# RXV2.net
KiCad netlist of a schematic drawn in EAGLE
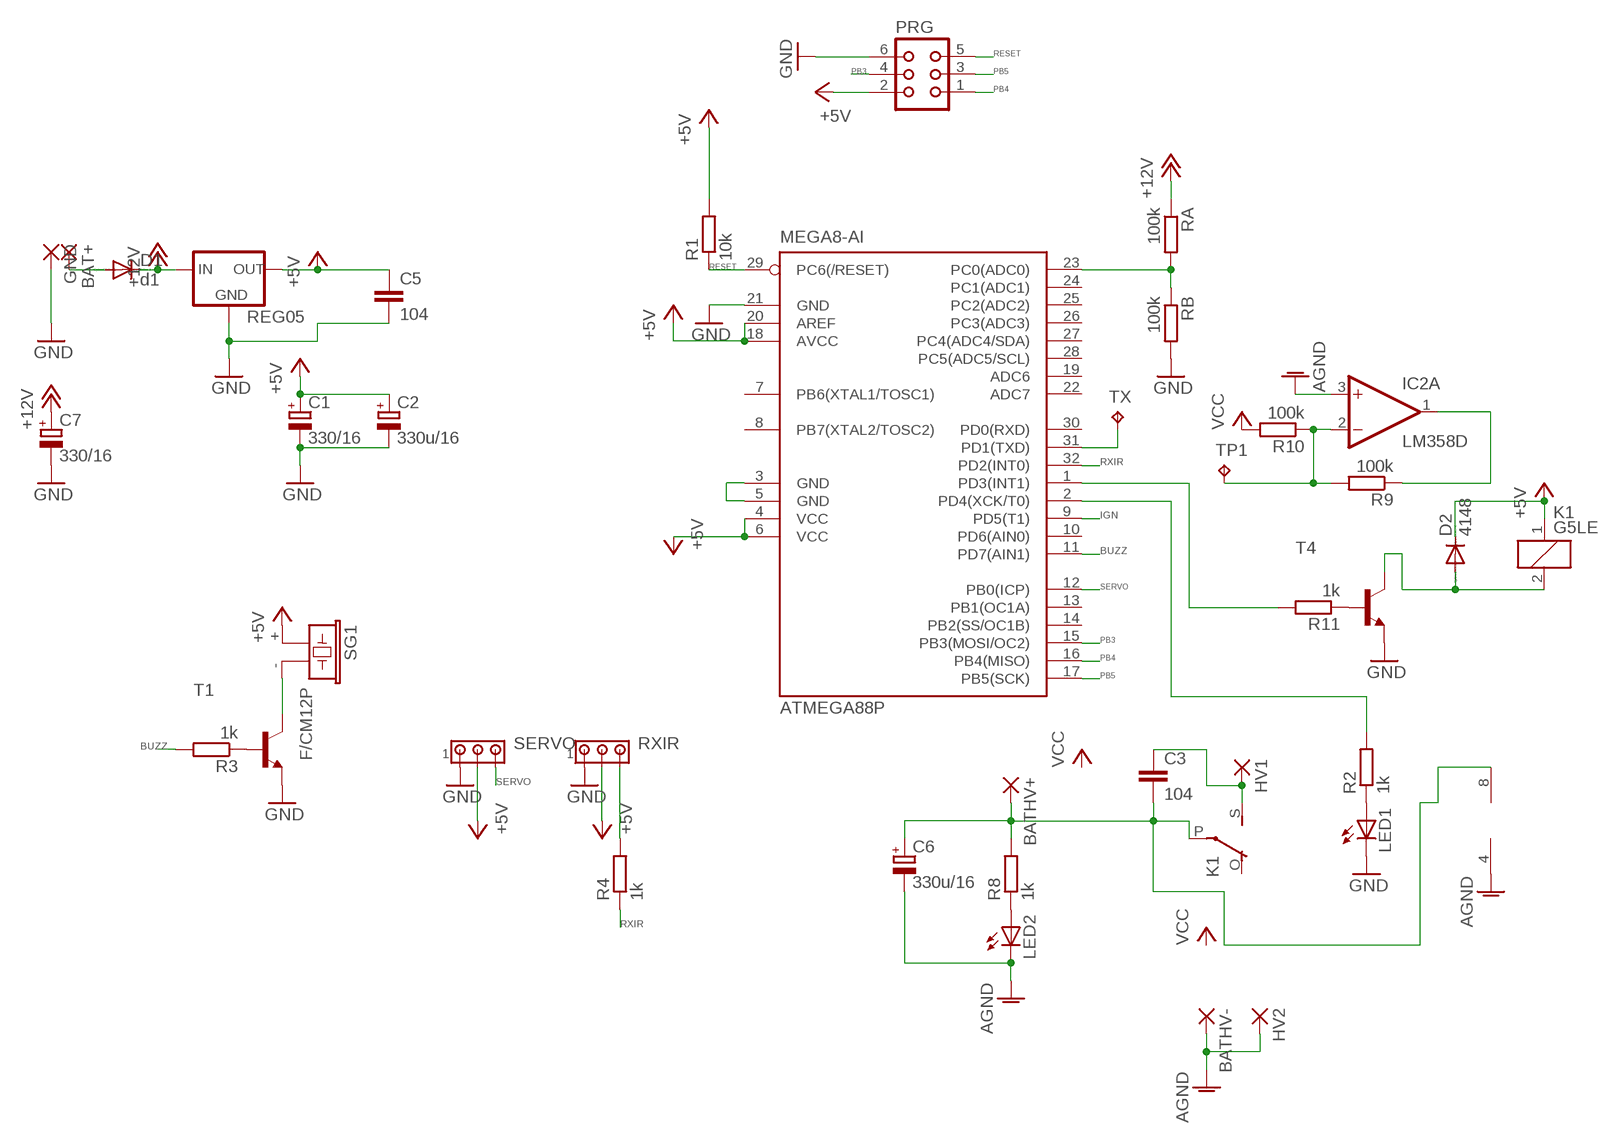
[diagram p0: schematic, sheet 1]

(export (version "E")
  (design (tool "Eeschema 10.0.6"))
  (components
    (comp (ref "ATMEGA88P")
      (value "MEGA8-AI")
      (footprint "eagle-import:TQFP32-08")
      (fields (field (name "MPN") "ATMEGA8-16AU"))
      (libsource (lib "eagle-import") (part "MEGA8-AI"))
    )
    (comp (ref "BAT+")
      (value "SMD5")
      (footprint "eagle-import:SMD2,54-5,08")
      (libsource (lib "eagle-import") (part "SMD5"))
    )
    (comp (ref "BATHV+")
      (value "SMD5")
      (footprint "eagle-import:SMD2,54-5,08")
      (libsource (lib "eagle-import") (part "SMD5"))
    )
    (comp (ref "BATHV-")
      (value "SMD5")
      (footprint "eagle-import:SMD2,54-5,08")
      (libsource (lib "eagle-import") (part "SMD5"))
    )
    (comp (ref "C1")
      (value "330/16")
      (footprint "eagle-import:E2,5-7")
      (libsource (lib "eagle-import") (part "CPOL-EUE2.5-7"))
    )
    (comp (ref "C2")
      (value "330u/16")
      (footprint "eagle-import:E2,5-6")
      (libsource (lib "eagle-import") (part "CPOL-EUE2.5-6"))
    )
    (comp (ref "C3")
      (value "104")
      (footprint "eagle-import:C0805")
      (libsource (lib "eagle-import") (part "C-EUC0805"))
    )
    (comp (ref "C5")
      (value "104")
      (footprint "eagle-import:C2.5-2")
      (libsource (lib "eagle-import") (part "C2.5/2"))
    )
    (comp (ref "C6")
      (value "330u/16")
      (footprint "eagle-import:E2,5-6")
      (libsource (lib "eagle-import") (part "CPOL-EUE2.5-6"))
    )
    (comp (ref "C7")
      (value "330/16")
      (footprint "eagle-import:E2,5-7")
      (libsource (lib "eagle-import") (part "CPOL-EUE2.5-7"))
    )
    (comp (ref "D1")
      (value "d1")
      (footprint "eagle-import:SOD-123_MINI-SMA")
      (libsource (lib "eagle-import") (part "CGRM400-G7"))
    )
    (comp (ref "D2")
      (value "4148")
      (footprint "eagle-import:DO35-7")
      (libsource (lib "eagle-import") (part "1N4148DO35-7"))
    )
    (comp (ref "GND")
      (value "SMD5")
      (footprint "eagle-import:SMD2,54-5,08")
      (libsource (lib "eagle-import") (part "SMD5"))
    )
    (comp (ref "HV1")
      (value "SMD5")
      (footprint "eagle-import:SMD2,54-5,08")
      (libsource (lib "eagle-import") (part "SMD5"))
    )
    (comp (ref "HV2")
      (value "SMD5")
      (footprint "eagle-import:SMD2,54-5,08")
      (libsource (lib "eagle-import") (part "SMD5"))
    )
    (comp (ref "IC2")
      (value "LM358D")
      (footprint "eagle-import:SO08")
      (libsource (lib "eagle-import") (part "LM358D"))
    )
    (comp (ref "K1")
      (value "G5LE")
      (footprint "eagle-import:G5LE")
      (libsource (lib "eagle-import") (part "G5LE"))
    )
    (comp (ref "LED1")
      (value "LEDCHIPLED_0805")
      (footprint "eagle-import:CHIPLED_0805")
      (libsource (lib "eagle-import") (part "LEDCHIPLED_0805"))
    )
    (comp (ref "LED2")
      (value "LEDCHIPLED_0805")
      (footprint "eagle-import:CHIPLED_0805")
      (libsource (lib "eagle-import") (part "LEDCHIPLED_0805"))
    )
    (comp (ref "PRG")
      (value "CON06")
      (footprint "eagle-import:CON06")
      (libsource (lib "eagle-import") (part "CON06"))
    )
    (comp (ref "R1")
      (value "10k")
      (footprint "eagle-import:M1206")
      (libsource (lib "eagle-import") (part "R-EU_M1206"))
    )
    (comp (ref "R2")
      (value "1k")
      (footprint "eagle-import:M1206")
      (libsource (lib "eagle-import") (part "R-EU_M1206"))
    )
    (comp (ref "R3")
      (value "1k")
      (footprint "eagle-import:M1206")
      (libsource (lib "eagle-import") (part "R-EU_M1206"))
    )
    (comp (ref "R4")
      (value "1k")
      (footprint "eagle-import:M1206")
      (libsource (lib "eagle-import") (part "R-EU_M1206"))
    )
    (comp (ref "R8")
      (value "1k")
      (footprint "eagle-import:M1206")
      (libsource (lib "eagle-import") (part "R-EU_M1206"))
    )
    (comp (ref "R9")
      (value "100k")
      (footprint "eagle-import:M1206")
      (libsource (lib "eagle-import") (part "R-EU_M1206"))
    )
    (comp (ref "R10")
      (value "100k")
      (footprint "eagle-import:M1206")
      (libsource (lib "eagle-import") (part "R-EU_M1206"))
    )
    (comp (ref "R11")
      (value "1k")
      (footprint "eagle-import:M1206")
      (libsource (lib "eagle-import") (part "R-EU_M1206"))
    )
    (comp (ref "RA")
      (value "100k")
      (footprint "eagle-import:M1206")
      (libsource (lib "eagle-import") (part "R-EU_M1206"))
    )
    (comp (ref "RB")
      (value "100k")
      (footprint "eagle-import:M1206")
      (libsource (lib "eagle-import") (part "R-EU_M1206"))
    )
    (comp (ref "REG05")
      (value "78XXS")
      (footprint "eagle-import:78XXS")
      (libsource (lib "eagle-import") (part "78XXS"))
    )
    (comp (ref "RXIR")
      (value "MTA03-100")
      (footprint "eagle-import:10X03MTA")
      (libsource (lib "eagle-import") (part "MTA03-100"))
    )
    (comp (ref "SERVO")
      (value "MTA03-100")
      (footprint "eagle-import:10X03MTA")
      (libsource (lib "eagle-import") (part "MTA03-100"))
    )
    (comp (ref "SG1")
      (value "F/CM12P")
      (footprint "eagle-import:F_CM12P")
      (libsource (lib "eagle-import") (part "F/CM12P"))
    )
    (comp (ref "T1")
      (value "MMBT2222ALT1-NPN-SOT23-BEC")
      (footprint "eagle-import:SOT23-BEC")
      (libsource (lib "eagle-import") (part "-NPN-SOT23-BECMMBT2222ALT1"))
    )
    (comp (ref "T4")
      (value "MMBT2222ALT1-NPN-SOT23-BEC")
      (footprint "eagle-import:SOT23-BEC")
      (libsource (lib "eagle-import") (part "-NPN-SOT23-BECMMBT2222ALT1"))
    )
    (comp (ref "TP1")
      (value "TPTP19R")
      (footprint "eagle-import:TP19R")
      (libsource (lib "eagle-import") (part "TPTP19R"))
    )
    (comp (ref "TX")
      (value "TPTP19R")
      (footprint "eagle-import:TP19R")
      (libsource (lib "eagle-import") (part "TPTP19R"))
    )
  )
  (nets
    (net (code "1") (name "+5V") (class "Default")
      (node (ref "ATMEGA88P") (pin "18") (pinfunction "AVCC_18") (pintype "power_in"))
      (node (ref "ATMEGA88P") (pin "20") (pinfunction "AREF_20") (pintype "passive"))
      (node (ref "ATMEGA88P") (pin "4") (pinfunction "VCC_4") (pintype "power_in"))
      (node (ref "ATMEGA88P") (pin "6") (pinfunction "VCC_6") (pintype "power_in"))
      (node (ref "C1") (pin "+") (pinfunction "+_+") (pintype "passive"))
      (node (ref "C2") (pin "+") (pinfunction "+_+") (pintype "passive"))
      (node (ref "C5") (pin "1") (pinfunction "1_1") (pintype "passive"))
      (node (ref "D2") (pin "C") (pinfunction "C_C") (pintype "passive"))
      (node (ref "K1") (pin "1") (pinfunction "1_1") (pintype "passive"))
      (node (ref "PRG") (pin "2") (pinfunction "2_2") (pintype "passive"))
      (node (ref "R1") (pin "2") (pinfunction "2_2") (pintype "passive"))
      (node (ref "REG05") (pin "OUT") (pinfunction "OUT_OUT") (pintype "passive"))
      (node (ref "RXIR") (pin "2") (pinfunction "2_2") (pintype "passive"))
      (node (ref "SERVO") (pin "2") (pinfunction "2_2") (pintype "passive"))
      (node (ref "SG1") (pin "+") (pinfunction "1_+") (pintype "passive"))
    )
    (net (code "2") (name "+12V") (class "Default")
      (node (ref "C7") (pin "+") (pinfunction "+_+") (pintype "passive"))
      (node (ref "D1") (pin "C") (pinfunction "C_C") (pintype "passive"))
      (node (ref "RA") (pin "1") (pinfunction "1_1") (pintype "passive"))
      (node (ref "REG05") (pin "IN") (pinfunction "IN_IN") (pintype "input"))
    )
    (net (code "3") (name "/BUZZ") (class "Default")
      (node (ref "ATMEGA88P") (pin "11") (pinfunction "PD7(AIN1)_11") (pintype "bidirectional"))
      (node (ref "R3") (pin "2") (pinfunction "2_2") (pintype "passive"))
    )
    (net (code "4") (name "/IGN") (class "Default")
      (node (ref "ATMEGA88P") (pin "9") (pinfunction "PD5(T1)_9") (pintype "bidirectional"))
    )
    (net (code "5") (name "/PB3") (class "Default")
      (node (ref "ATMEGA88P") (pin "15") (pinfunction "PB3(MOSI/OC2)_15") (pintype "bidirectional"))
      (node (ref "PRG") (pin "4") (pinfunction "4_4") (pintype "passive"))
    )
    (net (code "6") (name "/PB4") (class "Default")
      (node (ref "ATMEGA88P") (pin "16") (pinfunction "PB4(MISO)_16") (pintype "bidirectional"))
      (node (ref "PRG") (pin "1") (pinfunction "1_1") (pintype "passive"))
    )
    (net (code "7") (name "/PB5") (class "Default")
      (node (ref "ATMEGA88P") (pin "17") (pinfunction "PB5(SCK)_17") (pintype "bidirectional"))
      (node (ref "PRG") (pin "3") (pinfunction "3_3") (pintype "passive"))
    )
    (net (code "8") (name "/RESET") (class "Default")
      (node (ref "ATMEGA88P") (pin "29") (pinfunction "PC6(/RESET)_29") (pintype "bidirectional"))
      (node (ref "PRG") (pin "5") (pinfunction "5_5") (pintype "passive"))
      (node (ref "R1") (pin "1") (pinfunction "1_1") (pintype "passive"))
    )
    (net (code "9") (name "/RXIR") (class "Default")
      (node (ref "ATMEGA88P") (pin "32") (pinfunction "PD2(INT0)_32") (pintype "bidirectional"))
      (node (ref "R4") (pin "1") (pinfunction "1_1") (pintype "passive"))
    )
    (net (code "10") (name "/SERVO") (class "Default")
      (node (ref "ATMEGA88P") (pin "12") (pinfunction "PB0(ICP)_12") (pintype "bidirectional"))
      (node (ref "SERVO") (pin "3") (pinfunction "3_3") (pintype "passive"))
    )
    (net (code "11") (name "AGND") (class "Default")
      (node (ref "BATHV-") (pin "1") (pinfunction "P_1") (pintype "passive"))
      (node (ref "C6") (pin "-") (pinfunction "-_-") (pintype "passive"))
      (node (ref "HV2") (pin "1") (pinfunction "P_1") (pintype "passive"))
      (node (ref "IC2") (pin "3") (pinfunction "+IN_3") (pintype "input"))
      (node (ref "IC2") (pin "4") (pinfunction "V-_4") (pintype "power_in"))
      (node (ref "LED2") (pin "C") (pinfunction "C_C") (pintype "passive"))
    )
    (net (code "12") (name "GND") (class "Default")
      (node (ref "ATMEGA88P") (pin "21") (pinfunction "GND_21") (pintype "power_in"))
      (node (ref "C1") (pin "-") (pinfunction "-_-") (pintype "passive"))
      (node (ref "C2") (pin "-") (pinfunction "-_-") (pintype "passive"))
      (node (ref "C5") (pin "2") (pinfunction "2_2") (pintype "passive"))
      (node (ref "C7") (pin "-") (pinfunction "-_-") (pintype "passive"))
      (node (ref "GND") (pin "1") (pinfunction "P_1") (pintype "passive"))
      (node (ref "LED1") (pin "C") (pinfunction "C_C") (pintype "passive"))
      (node (ref "PRG") (pin "6") (pinfunction "6_6") (pintype "passive"))
      (node (ref "RB") (pin "2") (pinfunction "2_2") (pintype "passive"))
      (node (ref "REG05") (pin "GND") (pinfunction "GND_GND") (pintype "input"))
      (node (ref "RXIR") (pin "1") (pinfunction "1_1") (pintype "passive"))
      (node (ref "SERVO") (pin "1") (pinfunction "1_1") (pintype "passive"))
      (node (ref "T1") (pin "E") (pinfunction "E_E") (pintype "passive"))
      (node (ref "T4") (pin "E") (pinfunction "E_E") (pintype "passive"))
    )
    (net (code "13") (name "Net-(ATMEGA88P-GND-Pad3)") (class "Default")
      (node (ref "ATMEGA88P") (pin "3") (pinfunction "GND_3") (pintype "power_in"))
      (node (ref "ATMEGA88P") (pin "5") (pinfunction "GND_5") (pintype "power_in"))
    )
    (net (code "14") (name "Net-(ATMEGA88P-PC0(ADC0))") (class "Default")
      (node (ref "ATMEGA88P") (pin "23") (pinfunction "PC0(ADC0)_23") (pintype "bidirectional"))
      (node (ref "RA") (pin "2") (pinfunction "2_2") (pintype "passive"))
      (node (ref "RB") (pin "1") (pinfunction "1_1") (pintype "passive"))
    )
    (net (code "15") (name "Net-(ATMEGA88P-PD1(TXD))") (class "Default")
      (node (ref "ATMEGA88P") (pin "31") (pinfunction "PD1(TXD)_31") (pintype "bidirectional"))
      (node (ref "TX") (pin "TP") (pinfunction "TP_TP") (pintype "input"))
    )
    (net (code "16") (name "Net-(ATMEGA88P-PD3(INT1))") (class "Default")
      (node (ref "ATMEGA88P") (pin "1") (pinfunction "PD3(INT1)_1") (pintype "bidirectional"))
      (node (ref "R11") (pin "2") (pinfunction "2_2") (pintype "passive"))
    )
    (net (code "17") (name "Net-(ATMEGA88P-PD4(XCK{slash}T0))") (class "Default")
      (node (ref "ATMEGA88P") (pin "2") (pinfunction "PD4(XCK/T0)_2") (pintype "bidirectional"))
      (node (ref "R2") (pin "2") (pinfunction "2_2") (pintype "passive"))
    )
    (net (code "18") (name "Net-(BAT+-P)") (class "Default")
      (node (ref "BAT+") (pin "1") (pinfunction "P_1") (pintype "passive"))
      (node (ref "D1") (pin "A") (pinfunction "A_A") (pintype "passive"))
    )
    (net (code "19") (name "Net-(BATHV+-P)") (class "Default")
      (node (ref "BATHV+") (pin "1") (pinfunction "P_1") (pintype "passive"))
      (node (ref "C3") (pin "2") (pinfunction "2_2") (pintype "passive"))
      (node (ref "C6") (pin "+") (pinfunction "+_+") (pintype "passive"))
      (node (ref "IC2") (pin "8") (pinfunction "V+_8") (pintype "power_in"))
      (node (ref "K1") (pin "P") (pinfunction "P_P") (pintype "passive"))
      (node (ref "R8") (pin "2") (pinfunction "2_2") (pintype "passive"))
    )
    (net (code "20") (name "Net-(D2-PadA)") (class "Default")
      (node (ref "D2") (pin "A") (pinfunction "A_A") (pintype "passive"))
      (node (ref "K1") (pin "2") (pinfunction "2_2") (pintype "passive"))
      (node (ref "T4") (pin "C") (pinfunction "C_C") (pintype "passive"))
    )
    (net (code "21") (name "Net-(HV1-P)") (class "Default")
      (node (ref "C3") (pin "1") (pinfunction "1_1") (pintype "passive"))
      (node (ref "HV1") (pin "1") (pinfunction "P_1") (pintype "passive"))
      (node (ref "K1") (pin "S") (pinfunction "S_S") (pintype "passive"))
    )
    (net (code "22") (name "Net-(IC2A--IN)") (class "Default")
      (node (ref "IC2") (pin "2") (pinfunction "-IN_2") (pintype "input"))
      (node (ref "R10") (pin "1") (pinfunction "1_1") (pintype "passive"))
      (node (ref "R9") (pin "2") (pinfunction "2_2") (pintype "passive"))
      (node (ref "TP1") (pin "TP") (pinfunction "TP_TP") (pintype "input"))
    )
    (net (code "23") (name "Net-(IC2A-OUT)") (class "Default")
      (node (ref "IC2") (pin "1") (pinfunction "OUT_1") (pintype "output"))
      (node (ref "R9") (pin "1") (pinfunction "1_1") (pintype "passive"))
    )
    (net (code "24") (name "Net-(LED1-PadA)") (class "Default")
      (node (ref "LED1") (pin "A") (pinfunction "A_A") (pintype "passive"))
      (node (ref "R2") (pin "1") (pinfunction "1_1") (pintype "passive"))
    )
    (net (code "25") (name "Net-(LED2-PadA)") (class "Default")
      (node (ref "LED2") (pin "A") (pinfunction "A_A") (pintype "passive"))
      (node (ref "R8") (pin "1") (pinfunction "1_1") (pintype "passive"))
    )
    (net (code "26") (name "Net-(R3-Pad1)") (class "Default")
      (node (ref "R3") (pin "1") (pinfunction "1_1") (pintype "passive"))
      (node (ref "T1") (pin "B") (pinfunction "B_B") (pintype "passive"))
    )
    (net (code "27") (name "Net-(R4-Pad2)") (class "Default")
      (node (ref "R4") (pin "2") (pinfunction "2_2") (pintype "passive"))
      (node (ref "RXIR") (pin "3") (pinfunction "3_3") (pintype "passive"))
    )
    (net (code "28") (name "Net-(R11-Pad1)") (class "Default")
      (node (ref "R11") (pin "1") (pinfunction "1_1") (pintype "passive"))
      (node (ref "T4") (pin "B") (pinfunction "B_B") (pintype "passive"))
    )
    (net (code "29") (name "Net-(SG1-2)") (class "Default")
      (node (ref "SG1") (pin "-") (pinfunction "2_-") (pintype "passive"))
      (node (ref "T1") (pin "C") (pinfunction "C_C") (pintype "passive"))
    )
    (net (code "30") (name "VCC") (class "Default")
      (node (ref "R10") (pin "2") (pinfunction "2_2") (pintype "passive"))
    )
    (net (code "31") (name "unconnected-(ATMEGA88P-ADC6-Pad19)") (class "Default")
      (node (ref "ATMEGA88P") (pin "19") (pinfunction "ADC6_19") (pintype "bidirectional"))
    )
    (net (code "32") (name "unconnected-(ATMEGA88P-ADC7-Pad22)") (class "Default")
      (node (ref "ATMEGA88P") (pin "22") (pinfunction "ADC7_22") (pintype "bidirectional"))
    )
    (net (code "33") (name "unconnected-(ATMEGA88P-PB1(OC1A)-Pad13)") (class "Default")
      (node (ref "ATMEGA88P") (pin "13") (pinfunction "PB1(OC1A)_13") (pintype "bidirectional"))
    )
    (net (code "34") (name "unconnected-(ATMEGA88P-PB2(SS{slash}OC1B)-Pad14)") (class "Default")
      (node (ref "ATMEGA88P") (pin "14") (pinfunction "PB2(SS/OC1B)_14") (pintype "bidirectional"))
    )
    (net (code "35") (name "unconnected-(ATMEGA88P-PB6(XTAL1{slash}TOSC1)-Pad7)") (class "Default")
      (node (ref "ATMEGA88P") (pin "7") (pinfunction "PB6(XTAL1/TOSC1)_7") (pintype "bidirectional"))
    )
    (net (code "36") (name "unconnected-(ATMEGA88P-PB7(XTAL2{slash}TOSC2)-Pad8)") (class "Default")
      (node (ref "ATMEGA88P") (pin "8") (pinfunction "PB7(XTAL2/TOSC2)_8") (pintype "bidirectional"))
    )
    (net (code "37") (name "unconnected-(ATMEGA88P-PC1(ADC1)-Pad24)") (class "Default")
      (node (ref "ATMEGA88P") (pin "24") (pinfunction "PC1(ADC1)_24") (pintype "bidirectional"))
    )
    (net (code "38") (name "unconnected-(ATMEGA88P-PC2(ADC2)-Pad25)") (class "Default")
      (node (ref "ATMEGA88P") (pin "25") (pinfunction "PC2(ADC2)_25") (pintype "bidirectional"))
    )
    (net (code "39") (name "unconnected-(ATMEGA88P-PC3(ADC3)-Pad26)") (class "Default")
      (node (ref "ATMEGA88P") (pin "26") (pinfunction "PC3(ADC3)_26") (pintype "bidirectional"))
    )
    (net (code "40") (name "unconnected-(ATMEGA88P-PC4(ADC4{slash}SDA)-Pad27)") (class "Default")
      (node (ref "ATMEGA88P") (pin "27") (pinfunction "PC4(ADC4/SDA)_27") (pintype "bidirectional"))
    )
    (net (code "41") (name "unconnected-(ATMEGA88P-PC5(ADC5{slash}SCL)-Pad28)") (class "Default")
      (node (ref "ATMEGA88P") (pin "28") (pinfunction "PC5(ADC5/SCL)_28") (pintype "bidirectional"))
    )
    (net (code "42") (name "unconnected-(ATMEGA88P-PD0(RXD)-Pad30)") (class "Default")
      (node (ref "ATMEGA88P") (pin "30") (pinfunction "PD0(RXD)_30") (pintype "bidirectional"))
    )
    (net (code "43") (name "unconnected-(ATMEGA88P-PD6(AIN0)-Pad10)") (class "Default")
      (node (ref "ATMEGA88P") (pin "10") (pinfunction "PD6(AIN0)_10") (pintype "bidirectional"))
    )
    (net (code "44") (name "unconnected-(K1-PadO)") (class "Default")
      (node (ref "K1") (pin "O") (pinfunction "O_O") (pintype "passive"))
    )
  )
)
